# SmartBikeLight_Sch.net
KiCad netlist of a schematic drawn in Altium Designer
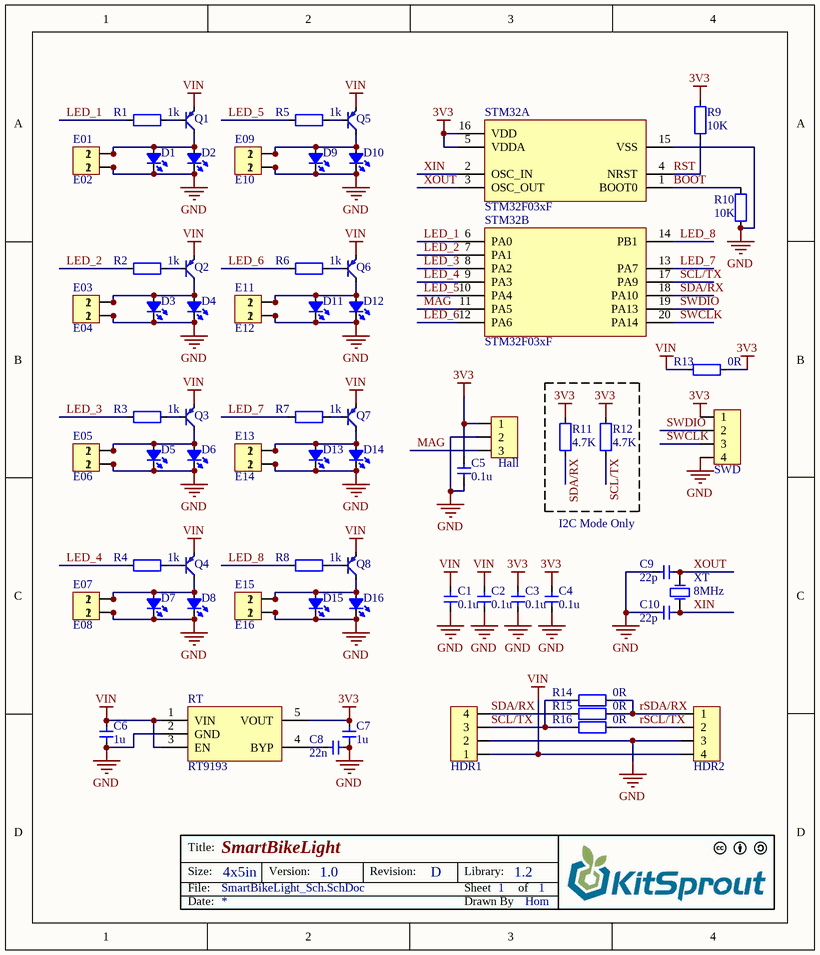
[diagram p0: SmartBikeLight_Sch.SchDoc]

(export (version "E")
  (design (tool "Eeschema 10.0.6"))
  (components
    (comp (ref "C1")
      (value "0.1u")
      (footprint "PCB_PassiveCap:CAP_0603")
      (description "Capacitor")
      (fields (field (name "Comment") "Cap_0603"))
      (libsource (lib "SCH_Passive") (part "Cap_0603"))
    )
    (comp (ref "C2")
      (value "0.1u")
      (footprint "PCB_PassiveCap:CAP_0603")
      (description "Capacitor")
      (fields (field (name "Comment") "Cap_0603"))
      (libsource (lib "SCH_Passive") (part "Cap_0603"))
    )
    (comp (ref "C3")
      (value "0.1u")
      (footprint "PCB_PassiveCap:CAP_0603")
      (description "Capacitor")
      (fields (field (name "Comment") "Cap_0603"))
      (libsource (lib "SCH_Passive") (part "Cap_0603"))
    )
    (comp (ref "C4")
      (value "0.1u")
      (footprint "PCB_PassiveCap:CAP_0603")
      (description "Capacitor")
      (fields (field (name "Comment") "Cap_0603"))
      (libsource (lib "SCH_Passive") (part "Cap_0603"))
    )
    (comp (ref "C5")
      (value "0.1u")
      (footprint "PCB_PassiveCap:CAP_0603")
      (description "Capacitor")
      (fields (field (name "Comment") "Cap_0603"))
      (libsource (lib "SCH_Passive") (part "Cap_0603"))
    )
    (comp (ref "C6")
      (value "1u")
      (footprint "PCB_PassiveCap:CAP_0603")
      (description "Capacitor")
      (fields (field (name "Comment") "Cap_0603"))
      (libsource (lib "SCH_Passive") (part "Cap_0603"))
    )
    (comp (ref "C7")
      (value "1u")
      (footprint "PCB_PassiveCap:CAP_0603")
      (description "Capacitor")
      (fields (field (name "Comment") "Cap_0603"))
      (libsource (lib "SCH_Passive") (part "Cap_0603"))
    )
    (comp (ref "C8")
      (value "22n")
      (footprint "PCB_PassiveCap:CAP_0603")
      (description "Capacitor")
      (fields (field (name "Comment") "Cap_0603"))
      (libsource (lib "SCH_Passive") (part "Cap_0603"))
    )
    (comp (ref "C9")
      (value "22p")
      (footprint "PCB_PassiveCap:CAP_0603")
      (description "Capacitor")
      (fields (field (name "Comment") "Cap_0603"))
      (libsource (lib "SCH_Passive") (part "Cap_0603"))
    )
    (comp (ref "C10")
      (value "22p")
      (footprint "PCB_PassiveCap:CAP_0603")
      (description "Capacitor")
      (fields (field (name "Comment") "Cap_0603"))
      (libsource (lib "SCH_Passive") (part "Cap_0603"))
    )
    (comp (ref "D1")
      (value "LED_5730")
      (footprint "PCB_ActiveLED:LED_5730_WHITE")
      (description "LED")
      (libsource (lib "SCH_Active") (part "LED_5730"))
    )
    (comp (ref "D2")
      (value "LED_5730")
      (footprint "PCB_ActiveLED:LED_5730_WHITE")
      (description "LED")
      (libsource (lib "SCH_Active") (part "LED_5730"))
    )
    (comp (ref "D3")
      (value "LED_5730")
      (footprint "PCB_ActiveLED:LED_5730_WHITE")
      (description "LED")
      (libsource (lib "SCH_Active") (part "LED_5730"))
    )
    (comp (ref "D4")
      (value "LED_5730")
      (footprint "PCB_ActiveLED:LED_5730_WHITE")
      (description "LED")
      (libsource (lib "SCH_Active") (part "LED_5730"))
    )
    (comp (ref "D5")
      (value "LED_5730")
      (footprint "PCB_ActiveLED:LED_5730_WHITE")
      (description "LED")
      (libsource (lib "SCH_Active") (part "LED_5730"))
    )
    (comp (ref "D6")
      (value "LED_5730")
      (footprint "PCB_ActiveLED:LED_5730_WHITE")
      (description "LED")
      (libsource (lib "SCH_Active") (part "LED_5730"))
    )
    (comp (ref "D7")
      (value "LED_5730")
      (footprint "PCB_ActiveLED:LED_5730_WHITE")
      (description "LED")
      (libsource (lib "SCH_Active") (part "LED_5730"))
    )
    (comp (ref "D8")
      (value "LED_5730")
      (footprint "PCB_ActiveLED:LED_5730_WHITE")
      (description "LED")
      (libsource (lib "SCH_Active") (part "LED_5730"))
    )
    (comp (ref "D9")
      (value "LED_5730")
      (footprint "PCB_ActiveLED:LED_5730_WHITE")
      (description "LED")
      (libsource (lib "SCH_Active") (part "LED_5730"))
    )
    (comp (ref "D10")
      (value "LED_5730")
      (footprint "PCB_ActiveLED:LED_5730_WHITE")
      (description "LED")
      (libsource (lib "SCH_Active") (part "LED_5730"))
    )
    (comp (ref "D11")
      (value "LED_5730")
      (footprint "PCB_ActiveLED:LED_5730_WHITE")
      (description "LED")
      (libsource (lib "SCH_Active") (part "LED_5730"))
    )
    (comp (ref "D12")
      (value "LED_5730")
      (footprint "PCB_ActiveLED:LED_5730_WHITE")
      (description "LED")
      (libsource (lib "SCH_Active") (part "LED_5730"))
    )
    (comp (ref "D13")
      (value "LED_5730")
      (footprint "PCB_ActiveLED:LED_5730_WHITE")
      (description "LED")
      (libsource (lib "SCH_Active") (part "LED_5730"))
    )
    (comp (ref "D14")
      (value "LED_5730")
      (footprint "PCB_ActiveLED:LED_5730_WHITE")
      (description "LED")
      (libsource (lib "SCH_Active") (part "LED_5730"))
    )
    (comp (ref "D15")
      (value "LED_5730")
      (footprint "PCB_ActiveLED:LED_5730_WHITE")
      (description "LED")
      (libsource (lib "SCH_Active") (part "LED_5730"))
    )
    (comp (ref "D16")
      (value "LED_5730")
      (footprint "PCB_ActiveLED:LED_5730_WHITE")
      (description "LED")
      (libsource (lib "SCH_Active") (part "LED_5730"))
    )
    (comp (ref "E01")
      (value "HDR1x2_1.27T")
      (footprint "PCB_ConnectorHDR:HDR1X2_1.27_180H")
      (description "Header")
      (libsource (lib "SCH_ConnectorHDR") (part "HDR1x2_1.27T"))
    )
    (comp (ref "E02")
      (value "HDR1x2_1.27")
      (footprint "PCB_ConnectorHDR:HDR1X2_1.27_180H")
      (description "Header")
      (libsource (lib "SCH_ConnectorHDR") (part "HDR1x2_1.27"))
    )
    (comp (ref "E03")
      (value "HDR1x2_1.27T")
      (footprint "PCB_ConnectorHDR:HDR1X2_1.27_180H")
      (description "Header")
      (libsource (lib "SCH_ConnectorHDR") (part "HDR1x2_1.27T"))
    )
    (comp (ref "E04")
      (value "HDR1x2_1.27")
      (footprint "PCB_ConnectorHDR:HDR1X2_1.27_180H")
      (description "Header")
      (libsource (lib "SCH_ConnectorHDR") (part "HDR1x2_1.27"))
    )
    (comp (ref "E05")
      (value "HDR1x2_1.27T")
      (footprint "PCB_ConnectorHDR:HDR1X2_1.27_180H")
      (description "Header")
      (libsource (lib "SCH_ConnectorHDR") (part "HDR1x2_1.27T"))
    )
    (comp (ref "E06")
      (value "HDR1x2_1.27")
      (footprint "PCB_ConnectorHDR:HDR1X2_1.27_180H")
      (description "Header")
      (libsource (lib "SCH_ConnectorHDR") (part "HDR1x2_1.27"))
    )
    (comp (ref "E07")
      (value "HDR1x2_1.27T")
      (footprint "PCB_ConnectorHDR:HDR1X2_1.27_180H")
      (description "Header")
      (libsource (lib "SCH_ConnectorHDR") (part "HDR1x2_1.27T"))
    )
    (comp (ref "E08")
      (value "HDR1x2_1.27")
      (footprint "PCB_ConnectorHDR:HDR1X2_1.27_180H")
      (description "Header")
      (libsource (lib "SCH_ConnectorHDR") (part "HDR1x2_1.27"))
    )
    (comp (ref "E09")
      (value "HDR1x2_1.27T")
      (footprint "PCB_ConnectorHDR:HDR1X2_1.27_180H")
      (description "Header")
      (libsource (lib "SCH_ConnectorHDR") (part "HDR1x2_1.27T"))
    )
    (comp (ref "E10")
      (value "HDR1x2_1.27")
      (footprint "PCB_ConnectorHDR:HDR1X2_1.27_180H")
      (description "Header")
      (libsource (lib "SCH_ConnectorHDR") (part "HDR1x2_1.27"))
    )
    (comp (ref "E11")
      (value "HDR1x2_1.27T")
      (footprint "PCB_ConnectorHDR:HDR1X2_1.27_180H")
      (description "Header")
      (libsource (lib "SCH_ConnectorHDR") (part "HDR1x2_1.27T"))
    )
    (comp (ref "E12")
      (value "HDR1x2_1.27")
      (footprint "PCB_ConnectorHDR:HDR1X2_1.27_180H")
      (description "Header")
      (libsource (lib "SCH_ConnectorHDR") (part "HDR1x2_1.27"))
    )
    (comp (ref "E13")
      (value "HDR1x2_1.27T")
      (footprint "PCB_ConnectorHDR:HDR1X2_1.27_180H")
      (description "Header")
      (libsource (lib "SCH_ConnectorHDR") (part "HDR1x2_1.27T"))
    )
    (comp (ref "E14")
      (value "HDR1x2_1.27")
      (footprint "PCB_ConnectorHDR:HDR1X2_1.27_180H")
      (description "Header")
      (libsource (lib "SCH_ConnectorHDR") (part "HDR1x2_1.27"))
    )
    (comp (ref "E15")
      (value "HDR1x2_1.27T")
      (footprint "PCB_ConnectorHDR:HDR1X2_1.27_180H")
      (description "Header")
      (libsource (lib "SCH_ConnectorHDR") (part "HDR1x2_1.27T"))
    )
    (comp (ref "E16")
      (value "HDR1x2_1.27")
      (footprint "PCB_ConnectorHDR:HDR1X2_1.27_180H")
      (description "Header")
      (libsource (lib "SCH_ConnectorHDR") (part "HDR1x2_1.27"))
    )
    (comp (ref "Hall")
      (value "HDR1x3_2.54")
      (footprint "PCB_ConnectorHDR:HDR1X3_2.54_180")
      (description "Header")
      (libsource (lib "SCH_ConnectorHDR") (part "HDR1x3_2.54"))
    )
    (comp (ref "HDR1")
      (value "HDR1x4_1.27")
      (footprint "PCB_ConnectorHDR:HDR1X4_1.27_180HF")
      (description "Header")
      (libsource (lib "") (part "HDR1x4_1.27_1"))
    )
    (comp (ref "HDR2")
      (value "HDR1x4_1.27")
      (footprint "PCB_ConnectorHDR:HDR1X4_1.27_180H")
      (description "Header")
      (libsource (lib "SCH_ConnectorHDR") (part "HDR1x4_1.27"))
    )
    (comp (ref "Q1")
      (value "BJT_PNP")
      (footprint "PCB_IntegratedCircuit:SOT23-3")
      (description "Transistor")
      (libsource (lib "SCH_Active") (part "BJT_PNP"))
    )
    (comp (ref "Q2")
      (value "BJT_PNP")
      (footprint "PCB_IntegratedCircuit:SOT23-3")
      (description "Transistor")
      (libsource (lib "SCH_Active") (part "BJT_PNP"))
    )
    (comp (ref "Q3")
      (value "BJT_PNP")
      (footprint "PCB_IntegratedCircuit:SOT23-3")
      (description "Transistor")
      (libsource (lib "SCH_Active") (part "BJT_PNP"))
    )
    (comp (ref "Q4")
      (value "BJT_PNP")
      (footprint "PCB_IntegratedCircuit:SOT23-3")
      (description "Transistor")
      (libsource (lib "SCH_Active") (part "BJT_PNP"))
    )
    (comp (ref "Q5")
      (value "BJT_PNP")
      (footprint "PCB_IntegratedCircuit:SOT23-3")
      (description "Transistor")
      (libsource (lib "SCH_Active") (part "BJT_PNP"))
    )
    (comp (ref "Q6")
      (value "BJT_PNP")
      (footprint "PCB_IntegratedCircuit:SOT23-3")
      (description "Transistor")
      (libsource (lib "SCH_Active") (part "BJT_PNP"))
    )
    (comp (ref "Q7")
      (value "BJT_PNP")
      (footprint "PCB_IntegratedCircuit:SOT23-3")
      (description "Transistor")
      (libsource (lib "SCH_Active") (part "BJT_PNP"))
    )
    (comp (ref "Q8")
      (value "BJT_PNP")
      (footprint "PCB_IntegratedCircuit:SOT23-3")
      (description "Transistor")
      (libsource (lib "SCH_Active") (part "BJT_PNP"))
    )
    (comp (ref "R1")
      (value "1k")
      (footprint "PCB_PassiveRes:RES_0603")
      (description "Resistor")
      (fields (field (name "Comment") "Res_0603"))
      (libsource (lib "") (part "Res_0603_1"))
    )
    (comp (ref "R2")
      (value "1k")
      (footprint "PCB_PassiveRes:RES_0603")
      (description "Resistor")
      (fields (field (name "Comment") "Res_0603"))
      (libsource (lib "") (part "Res_0603_1"))
    )
    (comp (ref "R3")
      (value "1k")
      (footprint "PCB_PassiveRes:RES_0603")
      (description "Resistor")
      (fields (field (name "Comment") "Res_0603"))
      (libsource (lib "") (part "Res_0603_1"))
    )
    (comp (ref "R4")
      (value "1k")
      (footprint "PCB_PassiveRes:RES_0603")
      (description "Resistor")
      (fields (field (name "Comment") "Res_0603"))
      (libsource (lib "") (part "Res_0603_1"))
    )
    (comp (ref "R5")
      (value "1k")
      (footprint "PCB_PassiveRes:RES_0603")
      (description "Resistor")
      (fields (field (name "Comment") "Res_0603"))
      (libsource (lib "") (part "Res_0603_1"))
    )
    (comp (ref "R6")
      (value "1k")
      (footprint "PCB_PassiveRes:RES_0603")
      (description "Resistor")
      (fields (field (name "Comment") "Res_0603"))
      (libsource (lib "") (part "Res_0603_1"))
    )
    (comp (ref "R7")
      (value "1k")
      (footprint "PCB_PassiveRes:RES_0603")
      (description "Resistor")
      (fields (field (name "Comment") "Res_0603"))
      (libsource (lib "") (part "Res_0603_1"))
    )
    (comp (ref "R8")
      (value "1k")
      (footprint "PCB_PassiveRes:RES_0603")
      (description "Resistor")
      (fields (field (name "Comment") "Res_0603"))
      (libsource (lib "") (part "Res_0603_1"))
    )
    (comp (ref "R9")
      (value "10K")
      (footprint "PCB_PassiveRes:RES_0603")
      (description "Resistor")
      (fields (field (name "Comment") "Res_0603"))
      (libsource (lib "SCH_Passive") (part "Res_0603"))
    )
    (comp (ref "R10")
      (value "10K")
      (footprint "PCB_PassiveRes:RES_0603")
      (description "Resistor")
      (fields (field (name "Comment") "Res_0603"))
      (libsource (lib "SCH_Passive") (part "Res_0603"))
    )
    (comp (ref "R11")
      (value "4.7K")
      (footprint "PCB_PassiveRes:RES_0603")
      (description "Resistor")
      (fields (field (name "Comment") "Res_0603"))
      (libsource (lib "SCH_Passive") (part "Res_0603"))
    )
    (comp (ref "R12")
      (value "4.7K")
      (footprint "PCB_PassiveRes:RES_0603")
      (description "Resistor")
      (fields (field (name "Comment") "Res_0603"))
      (libsource (lib "SCH_Passive") (part "Res_0603"))
    )
    (comp (ref "R13")
      (value "0R")
      (footprint "PCB_PassiveRes:RES_0603")
      (description "Resistor")
      (fields (field (name "Comment") "Res_0603"))
      (libsource (lib "") (part "Res_0603_1"))
    )
    (comp (ref "R14")
      (value "0R")
      (footprint "PCB_PassiveRes:RES_0603")
      (description "Resistor")
      (fields (field (name "Comment") "Res_0603"))
      (libsource (lib "") (part "Res_0603_1"))
    )
    (comp (ref "R15")
      (value "0R")
      (footprint "PCB_PassiveRes:RES_0603")
      (description "Resistor")
      (fields (field (name "Comment") "Res_0603"))
      (libsource (lib "") (part "Res_0603_1"))
    )
    (comp (ref "R16")
      (value "0R")
      (footprint "PCB_PassiveRes:RES_0603")
      (description "Resistor")
      (fields (field (name "Comment") "Res_0603"))
      (libsource (lib "") (part "Res_0603_1"))
    )
    (comp (ref "RT")
      (value "RT9193")
      (footprint "PCB_IntegratedCircuit:SOT23-5")
      (description "Power")
      (libsource (lib "SCH_IntegratedCircuit") (part "RT9193"))
    )
    (comp (ref "STM32")
      (value "STM32F03xF")
      (footprint "PCB_IntegratedCircuit:TSSOP_E170_P0.65_20")
      (description "MCU")
      (libsource (lib "SCH_IntegratedCircuit") (part "STM32F03xF"))
    )
    (comp (ref "SWD")
      (value "HDR1x4_1.27")
      (footprint "PCB_ConnectorHDR:HDR1X4_1.27_180")
      (description "Header")
      (libsource (lib "SCH_ConnectorHDR") (part "HDR1x4_1.27"))
    )
    (comp (ref "XT")
      (value "8MHz")
      (footprint "PCB_Oscillator:XT_3225_2")
      (description "Crystal Oscillator")
      (fields (field (name "Comment") "XTAL_3225_2P"))
      (libsource (lib "SCH_Oscillator") (part "XTAL_3225_2P"))
    )
  )
  (nets
    (net (code "1") (name "/BOOT") (class "Default")
      (node (ref "R10") (pin "1") (pinfunction "1_1") (pintype "passive"))
      (node (ref "STM32") (pin "1") (pinfunction "BOOT0_1") (pintype "passive"))
    )
    (net (code "2") (name "/LED_1") (class "Default")
      (node (ref "R1") (pin "1") (pinfunction "1_1") (pintype "passive"))
      (node (ref "STM32") (pin "6") (pinfunction "PA0_6") (pintype "passive"))
    )
    (net (code "3") (name "/LED_2") (class "Default")
      (node (ref "R2") (pin "1") (pinfunction "1_1") (pintype "passive"))
      (node (ref "STM32") (pin "7") (pinfunction "PA1_7") (pintype "passive"))
    )
    (net (code "4") (name "/LED_3") (class "Default")
      (node (ref "R3") (pin "1") (pinfunction "1_1") (pintype "passive"))
      (node (ref "STM32") (pin "8") (pinfunction "PA2_8") (pintype "passive"))
    )
    (net (code "5") (name "/LED_4") (class "Default")
      (node (ref "R4") (pin "1") (pinfunction "1_1") (pintype "passive"))
      (node (ref "STM32") (pin "9") (pinfunction "PA3_9") (pintype "passive"))
    )
    (net (code "6") (name "/LED_5") (class "Default")
      (node (ref "R5") (pin "1") (pinfunction "1_1") (pintype "passive"))
      (node (ref "STM32") (pin "10") (pinfunction "PA4_10") (pintype "passive"))
    )
    (net (code "7") (name "/LED_6") (class "Default")
      (node (ref "R6") (pin "1") (pinfunction "1_1") (pintype "passive"))
      (node (ref "STM32") (pin "12") (pinfunction "PA6_12") (pintype "passive"))
    )
    (net (code "8") (name "/LED_7") (class "Default")
      (node (ref "R7") (pin "1") (pinfunction "1_1") (pintype "passive"))
      (node (ref "STM32") (pin "13") (pinfunction "PA7_13") (pintype "passive"))
    )
    (net (code "9") (name "/LED_8") (class "Default")
      (node (ref "R8") (pin "1") (pinfunction "1_1") (pintype "passive"))
      (node (ref "STM32") (pin "14") (pinfunction "PB1_14") (pintype "passive"))
    )
    (net (code "10") (name "/MAG") (class "Default")
      (node (ref "Hall") (pin "3") (pinfunction "3_3") (pintype "passive"))
      (node (ref "STM32") (pin "11") (pinfunction "PA5_11") (pintype "passive"))
    )
    (net (code "11") (name "/RST") (class "Default")
      (node (ref "R9") (pin "2") (pinfunction "2_2") (pintype "passive"))
      (node (ref "STM32") (pin "4") (pinfunction "NRST_4") (pintype "passive"))
    )
    (net (code "12") (name "/SCL{slash}TX") (class "Default")
      (node (ref "HDR1") (pin "3") (pinfunction "3_3") (pintype "passive"))
      (node (ref "R12") (pin "2") (pinfunction "2_2") (pintype "passive"))
      (node (ref "R14") (pin "1") (pinfunction "1_1") (pintype "passive"))
      (node (ref "R16") (pin "1") (pinfunction "1_1") (pintype "passive"))
      (node (ref "STM32") (pin "17") (pinfunction "PA9_17") (pintype "passive"))
    )
    (net (code "13") (name "/SDA{slash}RX") (class "Default")
      (node (ref "HDR1") (pin "4") (pinfunction "4_4") (pintype "passive"))
      (node (ref "R11") (pin "2") (pinfunction "2_2") (pintype "passive"))
      (node (ref "R15") (pin "1") (pinfunction "1_1") (pintype "passive"))
      (node (ref "STM32") (pin "18") (pinfunction "PA10_18") (pintype "passive"))
    )
    (net (code "14") (name "/SWCLK") (class "Default")
      (node (ref "STM32") (pin "20") (pinfunction "PA14_20") (pintype "passive"))
      (node (ref "SWD") (pin "3") (pinfunction "3_3") (pintype "passive"))
    )
    (net (code "15") (name "/SWDIO") (class "Default")
      (node (ref "STM32") (pin "19") (pinfunction "PA13_19") (pintype "passive"))
      (node (ref "SWD") (pin "2") (pinfunction "2_2") (pintype "passive"))
    )
    (net (code "16") (name "/XIN") (class "Default")
      (node (ref "C10") (pin "1") (pinfunction "1_1") (pintype "passive"))
      (node (ref "STM32") (pin "2") (pinfunction "OSC_IN_2") (pintype "passive"))
      (node (ref "XT") (pin "1") (pinfunction "OSC1_1") (pintype "passive"))
    )
    (net (code "17") (name "/XOUT") (class "Default")
      (node (ref "C9") (pin "1") (pinfunction "1_1") (pintype "passive"))
      (node (ref "STM32") (pin "3") (pinfunction "OSC_OUT_3") (pintype "passive"))
      (node (ref "XT") (pin "2") (pinfunction "OSC2_2") (pintype "passive"))
    )
    (net (code "18") (name "/rSCL{slash}TX") (class "Default")
      (node (ref "HDR2") (pin "2") (pinfunction "2_2") (pintype "passive"))
      (node (ref "R16") (pin "2") (pinfunction "2_2") (pintype "passive"))
    )
    (net (code "19") (name "/rSDA{slash}RX") (class "Default")
      (node (ref "HDR2") (pin "1") (pinfunction "1_1") (pintype "passive"))
      (node (ref "R14") (pin "2") (pinfunction "2_2") (pintype "passive"))
      (node (ref "R15") (pin "2") (pinfunction "2_2") (pintype "passive"))
    )
    (net (code "20") (name "3V3") (class "Default")
      (node (ref "C3") (pin "2") (pinfunction "2_2") (pintype "passive"))
      (node (ref "C4") (pin "2") (pinfunction "2_2") (pintype "passive"))
      (node (ref "C5") (pin "2") (pinfunction "2_2") (pintype "passive"))
      (node (ref "C7") (pin "2") (pinfunction "2_2") (pintype "passive"))
      (node (ref "Hall") (pin "1") (pinfunction "1_1") (pintype "passive"))
      (node (ref "R11") (pin "1") (pinfunction "1_1") (pintype "passive"))
      (node (ref "R12") (pin "1") (pinfunction "1_1") (pintype "passive"))
      (node (ref "R13") (pin "2") (pinfunction "2_2") (pintype "passive"))
      (node (ref "R9") (pin "1") (pinfunction "1_1") (pintype "passive"))
      (node (ref "RT") (pin "5") (pinfunction "VOUT_5") (pintype "passive"))
      (node (ref "STM32") (pin "16") (pinfunction "VDD_16") (pintype "passive"))
      (node (ref "STM32") (pin "5") (pinfunction "VDDA_5") (pintype "passive"))
      (node (ref "SWD") (pin "1") (pinfunction "1_1") (pintype "passive"))
    )
    (net (code "21") (name "GND") (class "Default")
      (node (ref "C1") (pin "1") (pinfunction "1_1") (pintype "passive"))
      (node (ref "C10") (pin "2") (pinfunction "2_2") (pintype "passive"))
      (node (ref "C2") (pin "1") (pinfunction "1_1") (pintype "passive"))
      (node (ref "C3") (pin "1") (pinfunction "1_1") (pintype "passive"))
      (node (ref "C4") (pin "1") (pinfunction "1_1") (pintype "passive"))
      (node (ref "C5") (pin "1") (pinfunction "1_1") (pintype "passive"))
      (node (ref "C6") (pin "1") (pinfunction "1_1") (pintype "passive"))
      (node (ref "C7") (pin "1") (pinfunction "1_1") (pintype "passive"))
      (node (ref "C8") (pin "1") (pinfunction "1_1") (pintype "passive"))
      (node (ref "C9") (pin "2") (pinfunction "2_2") (pintype "passive"))
      (node (ref "D1") (pin "2") (pinfunction "K_2") (pintype "passive"))
      (node (ref "D10") (pin "2") (pinfunction "K_2") (pintype "passive"))
      (node (ref "D11") (pin "2") (pinfunction "K_2") (pintype "passive"))
      (node (ref "D12") (pin "2") (pinfunction "K_2") (pintype "passive"))
      (node (ref "D13") (pin "2") (pinfunction "K_2") (pintype "passive"))
      (node (ref "D14") (pin "2") (pinfunction "K_2") (pintype "passive"))
      (node (ref "D15") (pin "2") (pinfunction "K_2") (pintype "passive"))
      (node (ref "D16") (pin "2") (pinfunction "K_2") (pintype "passive"))
      (node (ref "D2") (pin "2") (pinfunction "K_2") (pintype "passive"))
      (node (ref "D3") (pin "2") (pinfunction "K_2") (pintype "passive"))
      (node (ref "D4") (pin "2") (pinfunction "K_2") (pintype "passive"))
      (node (ref "D5") (pin "2") (pinfunction "K_2") (pintype "passive"))
      (node (ref "D6") (pin "2") (pinfunction "K_2") (pintype "passive"))
      (node (ref "D7") (pin "2") (pinfunction "K_2") (pintype "passive"))
      (node (ref "D8") (pin "2") (pinfunction "K_2") (pintype "passive"))
      (node (ref "D9") (pin "2") (pinfunction "K_2") (pintype "passive"))
      (node (ref "E01") (pin "2") (pinfunction "2_2") (pintype "passive"))
      (node (ref "E02") (pin "1") (pinfunction "1_1") (pintype "passive"))
      (node (ref "E03") (pin "2") (pinfunction "2_2") (pintype "passive"))
      (node (ref "E04") (pin "1") (pinfunction "1_1") (pintype "passive"))
      (node (ref "E05") (pin "2") (pinfunction "2_2") (pintype "passive"))
      (node (ref "E06") (pin "1") (pinfunction "1_1") (pintype "passive"))
      (node (ref "E07") (pin "2") (pinfunction "2_2") (pintype "passive"))
      (node (ref "E08") (pin "1") (pinfunction "1_1") (pintype "passive"))
      (node (ref "E09") (pin "2") (pinfunction "2_2") (pintype "passive"))
      (node (ref "E10") (pin "1") (pinfunction "1_1") (pintype "passive"))
      (node (ref "E11") (pin "2") (pinfunction "2_2") (pintype "passive"))
      (node (ref "E12") (pin "1") (pinfunction "1_1") (pintype "passive"))
      (node (ref "E13") (pin "2") (pinfunction "2_2") (pintype "passive"))
      (node (ref "E14") (pin "1") (pinfunction "1_1") (pintype "passive"))
      (node (ref "E15") (pin "2") (pinfunction "2_2") (pintype "passive"))
      (node (ref "E16") (pin "1") (pinfunction "1_1") (pintype "passive"))
      (node (ref "HDR1") (pin "2") (pinfunction "2_2") (pintype "passive"))
      (node (ref "HDR2") (pin "3") (pinfunction "3_3") (pintype "passive"))
      (node (ref "Hall") (pin "2") (pinfunction "2_2") (pintype "passive"))
      (node (ref "R10") (pin "2") (pinfunction "2_2") (pintype "passive"))
      (node (ref "RT") (pin "2") (pinfunction "GND_2") (pintype "passive"))
      (node (ref "STM32") (pin "15") (pinfunction "VSS_15") (pintype "passive"))
      (node (ref "SWD") (pin "4") (pinfunction "4_4") (pintype "passive"))
    )
    (net (code "22") (name "Net-(D1-A)") (class "Default")
      (node (ref "D1") (pin "1") (pinfunction "A_1") (pintype "passive"))
      (node (ref "D2") (pin "1") (pinfunction "A_1") (pintype "passive"))
      (node (ref "E01") (pin "1") (pinfunction "1_1") (pintype "passive"))
      (node (ref "E02") (pin "2") (pinfunction "2_2") (pintype "passive"))
      (node (ref "Q1") (pin "3") (pinfunction "C_3") (pintype "passive"))
    )
    (net (code "23") (name "Net-(D3-A)") (class "Default")
      (node (ref "D3") (pin "1") (pinfunction "A_1") (pintype "passive"))
      (node (ref "D4") (pin "1") (pinfunction "A_1") (pintype "passive"))
      (node (ref "E03") (pin "1") (pinfunction "1_1") (pintype "passive"))
      (node (ref "E04") (pin "2") (pinfunction "2_2") (pintype "passive"))
      (node (ref "Q2") (pin "3") (pinfunction "C_3") (pintype "passive"))
    )
    (net (code "24") (name "Net-(D5-A)") (class "Default")
      (node (ref "D5") (pin "1") (pinfunction "A_1") (pintype "passive"))
      (node (ref "D6") (pin "1") (pinfunction "A_1") (pintype "passive"))
      (node (ref "E05") (pin "1") (pinfunction "1_1") (pintype "passive"))
      (node (ref "E06") (pin "2") (pinfunction "2_2") (pintype "passive"))
      (node (ref "Q3") (pin "3") (pinfunction "C_3") (pintype "passive"))
    )
    (net (code "25") (name "Net-(D7-A)") (class "Default")
      (node (ref "D7") (pin "1") (pinfunction "A_1") (pintype "passive"))
      (node (ref "D8") (pin "1") (pinfunction "A_1") (pintype "passive"))
      (node (ref "E07") (pin "1") (pinfunction "1_1") (pintype "passive"))
      (node (ref "E08") (pin "2") (pinfunction "2_2") (pintype "passive"))
      (node (ref "Q4") (pin "3") (pinfunction "C_3") (pintype "passive"))
    )
    (net (code "26") (name "Net-(D10-A)") (class "Default")
      (node (ref "D10") (pin "1") (pinfunction "A_1") (pintype "passive"))
      (node (ref "D9") (pin "1") (pinfunction "A_1") (pintype "passive"))
      (node (ref "E09") (pin "1") (pinfunction "1_1") (pintype "passive"))
      (node (ref "E10") (pin "2") (pinfunction "2_2") (pintype "passive"))
      (node (ref "Q5") (pin "3") (pinfunction "C_3") (pintype "passive"))
    )
    (net (code "27") (name "Net-(D11-A)") (class "Default")
      (node (ref "D11") (pin "1") (pinfunction "A_1") (pintype "passive"))
      (node (ref "D12") (pin "1") (pinfunction "A_1") (pintype "passive"))
      (node (ref "E11") (pin "1") (pinfunction "1_1") (pintype "passive"))
      (node (ref "E12") (pin "2") (pinfunction "2_2") (pintype "passive"))
      (node (ref "Q6") (pin "3") (pinfunction "C_3") (pintype "passive"))
    )
    (net (code "28") (name "Net-(D13-A)") (class "Default")
      (node (ref "D13") (pin "1") (pinfunction "A_1") (pintype "passive"))
      (node (ref "D14") (pin "1") (pinfunction "A_1") (pintype "passive"))
      (node (ref "E13") (pin "1") (pinfunction "1_1") (pintype "passive"))
      (node (ref "E14") (pin "2") (pinfunction "2_2") (pintype "passive"))
      (node (ref "Q7") (pin "3") (pinfunction "C_3") (pintype "passive"))
    )
    (net (code "29") (name "Net-(D15-A)") (class "Default")
      (node (ref "D15") (pin "1") (pinfunction "A_1") (pintype "passive"))
      (node (ref "D16") (pin "1") (pinfunction "A_1") (pintype "passive"))
      (node (ref "E15") (pin "1") (pinfunction "1_1") (pintype "passive"))
      (node (ref "E16") (pin "2") (pinfunction "2_2") (pintype "passive"))
      (node (ref "Q8") (pin "3") (pinfunction "C_3") (pintype "passive"))
    )
    (net (code "30") (name "Net-(Q1-B)") (class "Default")
      (node (ref "Q1") (pin "1") (pinfunction "B_1") (pintype "passive"))
      (node (ref "R1") (pin "2") (pinfunction "2_2") (pintype "passive"))
    )
    (net (code "31") (name "Net-(Q2-B)") (class "Default")
      (node (ref "Q2") (pin "1") (pinfunction "B_1") (pintype "passive"))
      (node (ref "R2") (pin "2") (pinfunction "2_2") (pintype "passive"))
    )
    (net (code "32") (name "Net-(Q3-B)") (class "Default")
      (node (ref "Q3") (pin "1") (pinfunction "B_1") (pintype "passive"))
      (node (ref "R3") (pin "2") (pinfunction "2_2") (pintype "passive"))
    )
    (net (code "33") (name "Net-(Q4-B)") (class "Default")
      (node (ref "Q4") (pin "1") (pinfunction "B_1") (pintype "passive"))
      (node (ref "R4") (pin "2") (pinfunction "2_2") (pintype "passive"))
    )
    (net (code "34") (name "Net-(Q5-B)") (class "Default")
      (node (ref "Q5") (pin "1") (pinfunction "B_1") (pintype "passive"))
      (node (ref "R5") (pin "2") (pinfunction "2_2") (pintype "passive"))
    )
    (net (code "35") (name "Net-(Q6-B)") (class "Default")
      (node (ref "Q6") (pin "1") (pinfunction "B_1") (pintype "passive"))
      (node (ref "R6") (pin "2") (pinfunction "2_2") (pintype "passive"))
    )
    (net (code "36") (name "Net-(Q7-B)") (class "Default")
      (node (ref "Q7") (pin "1") (pinfunction "B_1") (pintype "passive"))
      (node (ref "R7") (pin "2") (pinfunction "2_2") (pintype "passive"))
    )
    (net (code "37") (name "Net-(Q8-B)") (class "Default")
      (node (ref "Q8") (pin "1") (pinfunction "B_1") (pintype "passive"))
      (node (ref "R8") (pin "2") (pinfunction "2_2") (pintype "passive"))
    )
    (net (code "38") (name "Net-(RT-BYP)") (class "Default")
      (node (ref "C8") (pin "2") (pinfunction "2_2") (pintype "passive"))
      (node (ref "RT") (pin "4") (pinfunction "BYP_4") (pintype "passive"))
    )
    (net (code "39") (name "VIN") (class "Default")
      (node (ref "C1") (pin "2") (pinfunction "2_2") (pintype "passive"))
      (node (ref "C2") (pin "2") (pinfunction "2_2") (pintype "passive"))
      (node (ref "C6") (pin "2") (pinfunction "2_2") (pintype "passive"))
      (node (ref "HDR1") (pin "1") (pinfunction "1_1") (pintype "passive"))
      (node (ref "HDR2") (pin "4") (pinfunction "4_4") (pintype "passive"))
      (node (ref "Q1") (pin "2") (pinfunction "E_2") (pintype "passive"))
      (node (ref "Q2") (pin "2") (pinfunction "E_2") (pintype "passive"))
      (node (ref "Q3") (pin "2") (pinfunction "E_2") (pintype "passive"))
      (node (ref "Q4") (pin "2") (pinfunction "E_2") (pintype "passive"))
      (node (ref "Q5") (pin "2") (pinfunction "E_2") (pintype "passive"))
      (node (ref "Q6") (pin "2") (pinfunction "E_2") (pintype "passive"))
      (node (ref "Q7") (pin "2") (pinfunction "E_2") (pintype "passive"))
      (node (ref "Q8") (pin "2") (pinfunction "E_2") (pintype "passive"))
      (node (ref "R13") (pin "1") (pinfunction "1_1") (pintype "passive"))
      (node (ref "RT") (pin "1") (pinfunction "VIN_1") (pintype "passive"))
      (node (ref "RT") (pin "3") (pinfunction "EN_3") (pintype "power_in"))
    )
  )
)
